# OBD-2_ESP32_Shield.net
KiCad netlist of a schematic drawn in Altium Designer
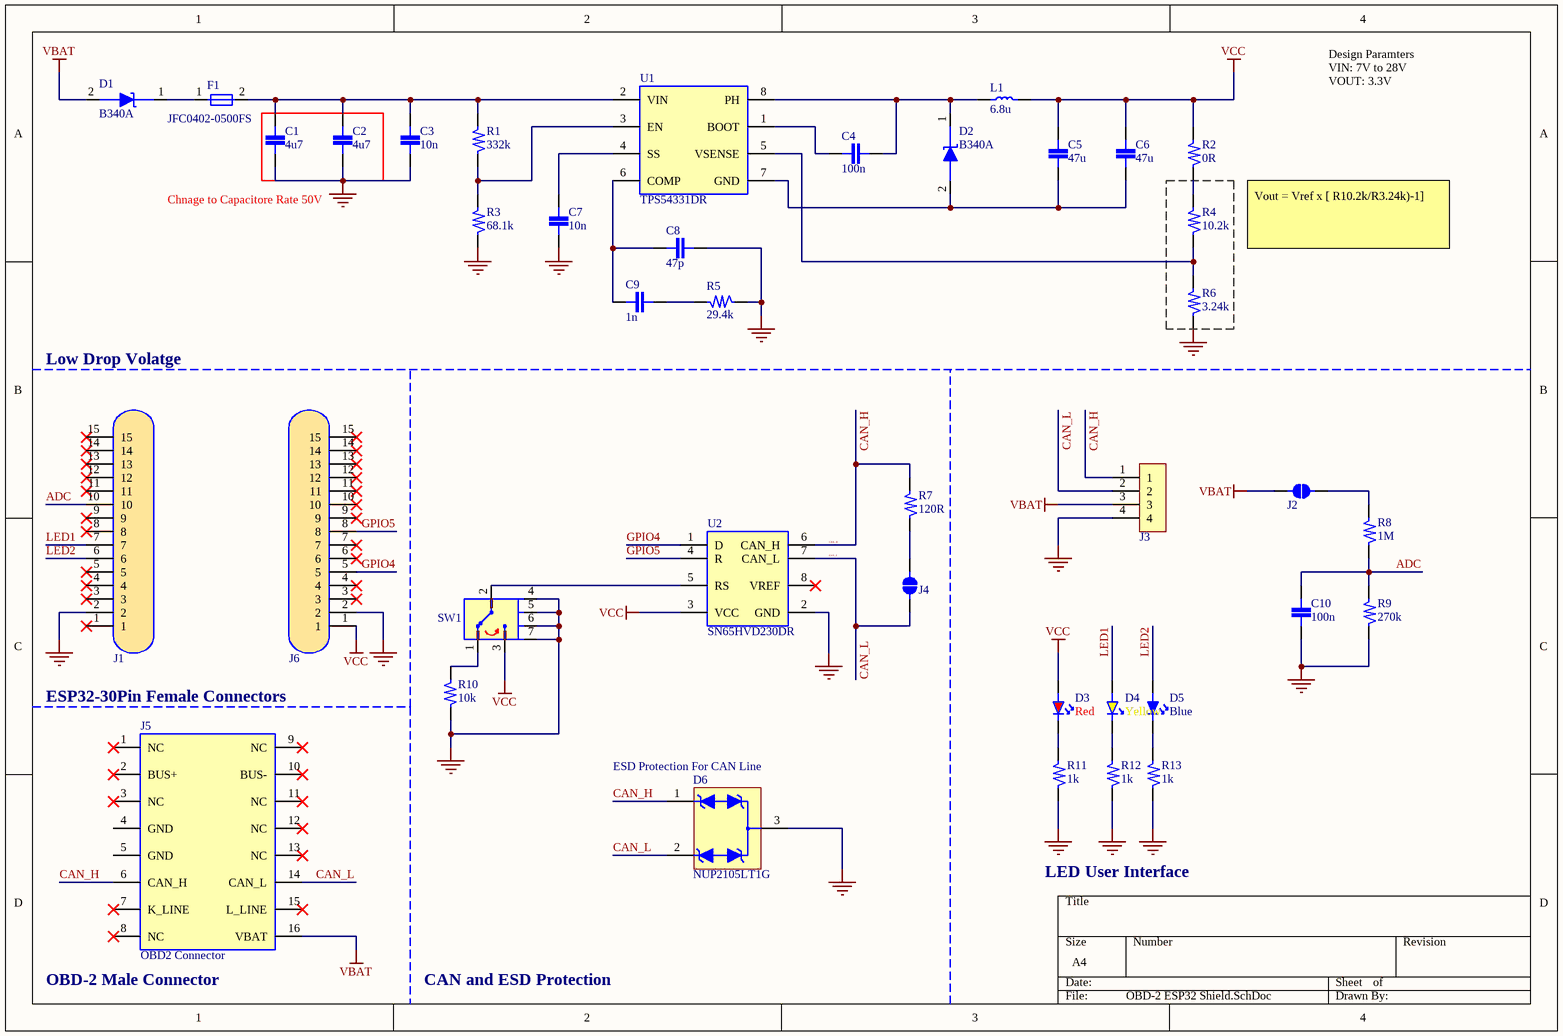
[diagram p0: OBD-2 ESP32 Shield.SchDoc]

(export (version "E")
  (design (tool "Eeschema 10.0.6"))
  (components
    (comp (ref "C1")
      (value "4u7")
      (footprint "CAP0402_1005")
      (description "25V 4.7uF X5R 0402 Multilayer Ceramic Capacitors MLCC - SMD/SMT ROHS")
      (fields (field (name "LCSC PART #") "C2858031") (field (name "MFR.PART #") "GRM155R61E475ME15D"))
      (libsource (lib "LeLibrary") (part "GRM155R61E475ME15D"))
    )
    (comp (ref "C2")
      (value "4u7")
      (footprint "CAP0402_1005")
      (description "25V 4.7uF X5R 0402 Multilayer Ceramic Capacitors MLCC - SMD/SMT ROHS")
      (fields (field (name "LCSC PART #") "C2858031") (field (name "MFR.PART #") "GRM155R61E475ME15D"))
      (libsource (lib "LeLibrary") (part "GRM155R61E475ME15D"))
    )
    (comp (ref "C3")
      (value "10n")
      (footprint "CAP0402_1005")
      (description "25V 10nF X7R ±10% 0402 Multilayer Ceramic Capacitors MLCC - SMD/SMT ROHS")
      (fields (field (name "LCSC PART #") "C77013") (field (name "MFR. PART #") "GRM155R71E103KA01D"))
      (libsource (lib "LeLibrary") (part "GRM155R71E103KA01D"))
    )
    (comp (ref "C4")
      (value "100n")
      (footprint "CAP0402_1005")
      (description "100V 100nF X5R ±10% 0402 Multilayer Ceramic Capacitors MLCC - SMD/SMT ROHS")
      (fields (field (name "LCSC PART #") "C162178") (field (name "MFR. PART #") "GRM155R62A104KE14D"))
      (libsource (lib "") (part "GRM155R62A104KE14D_1"))
    )
    (comp (ref "C5")
      (value "47u")
      (footprint "RES0603_1608")
      (description "6.3V 47uF X5R ±20% 0603 Multilayer Ceramic Capacitors MLCC - SMD/SMT ROHS")
      (fields (field (name "LCSC PART #") "C140782") (field (name "MFR. PART #") "GRM188R60J476ME15D"))
      (libsource (lib "LeLibrary") (part "GRM188R60J476ME15D"))
    )
    (comp (ref "C6")
      (value "47u")
      (footprint "RES0603_1608")
      (description "6.3V 47uF X5R ±20% 0603 Multilayer Ceramic Capacitors MLCC - SMD/SMT ROHS")
      (fields (field (name "LCSC PART #") "C140782") (field (name "MFR. PART #") "GRM188R60J476ME15D"))
      (libsource (lib "LeLibrary") (part "GRM188R60J476ME15D"))
    )
    (comp (ref "C7")
      (value "10n")
      (footprint "CAP0402_1005")
      (description "25V 10nF X7R ±10% 0402 Multilayer Ceramic Capacitors MLCC - SMD/SMT ROHS")
      (fields (field (name "LCSC PART #") "C77013") (field (name "MFR. PART #") "GRM155R71E103KA01D"))
      (libsource (lib "LeLibrary") (part "GRM155R71E103KA01D"))
    )
    (comp (ref "C8")
      (value "47p")
      (footprint "CAP0201_0603")
      (description "50V 47pF X7R ±10% 0201 Multilayer Ceramic Capacitors MLCC - SMD/SMT ROHS")
      (fields (field (name "LCSC PART #") "C576697") (field (name "MFR. PART #") "CC0201KRX7R9BB470"))
      (libsource (lib "LeLibrary") (part "CC0201KRX7R9BB470"))
    )
    (comp (ref "C9")
      (value "1n")
      (footprint "CAP0402_1005")
      (description "50V 1nF X8L ±10% 0402 Multilayer Ceramic Capacitors MLCC - SMD/SMT ROHS")
      (fields (field (name "MFR. PART #") "GCM155L81H102KA37D") (field (name "LCSC PART #") "C701290"))
      (libsource (lib "LeLibrary") (part "GCM155L81H102KA37D"))
    )
    (comp (ref "C10")
      (value "100n")
      (footprint "CAP0402_1005")
      (description "100V 100nF X5R ±10% 0402 Multilayer Ceramic Capacitors MLCC - SMD/SMT ROHS")
      (fields (field (name "LCSC PART #") "C162178") (field (name "MFR. PART #") "GRM155R62A104KE14D"))
      (libsource (lib "LeLibrary") (part "GRM155R62A104KE14D"))
    )
    (comp (ref "D1")
      (value "B340A")
      (footprint "SMA(DO-214AC)")
      (description "40V 3A 550mV@3A SMA(DO-214AC) Schottky Barrier Diodes (SBD) ROHS")
      (fields (field (name "LCSC PART #") "C3018525") (field (name "MFR.PART #") "B340A"))
      (libsource (lib "LeLibrary") (part "B340A"))
    )
    (comp (ref "D2")
      (value "B340A")
      (footprint "SMA(DO-214AC)")
      (description "40V 3A 550mV@3A SMA(DO-214AC) Schottky Barrier Diodes (SBD) ROHS")
      (fields (field (name "LCSC PART #") "C3018525") (field (name "MFR.PART #") "B340A"))
      (libsource (lib "LeLibrary") (part "B340A"))
    )
    (comp (ref "D3")
      (value "Red")
      (footprint "LED0603")
      (fields (field (name "LCSC PART #") "C965849") (field (name "MFR. PART #") "XL-TD1608SURC"))
      (libsource (lib "LeLibrary") (part "XL-TD1608SURC"))
    )
    (comp (ref "D4")
      (value "Yellow")
      (footprint "LED0603")
      (fields (field (name "LCSC PART #") "C965850") (field (name "MFR. PART #") "XL-TD1608UYC"))
      (libsource (lib "LeLibrary") (part "XL-TD1608UYC"))
    )
    (comp (ref "D5")
      (value "Blue")
      (footprint "LED0603")
      (fields (field (name "LCSC PART #") "C965853") (field (name "MFR. PART #") "XL-TD1608UBC"))
      (libsource (lib "LeLibrary") (part "XL-TD1608UBC"))
    )
    (comp (ref "D6")
      (value "NUP2105LT1G")
      (footprint "SOT-23")
      (description "SOT-23 Electrostatic and Surge Protection (TVS/ESD) ROHS")
      (fields (field (name "LCSC PART #") "C2890118") (field (name "MFR.PART #") "NUP2105LT1G"))
      (libsource (lib "LeLibrary") (part "NUP2105LT1G"))
    )
    (comp (ref "F1")
      (value "JFC0402-0500FS")
      (footprint "Fuse SMD 0402")
      (description "35A SMD Fuse 500mA 32V 32V 0402 Fuses ROHS")
      (fields (field (name "LCSC PART #") "C136320") (field (name "MFR.PART #") "JFC0402-0500FS"))
      (libsource (lib "LeLibrary") (part "JFC0402-0500FS"))
    )
    (comp (ref "J1")
      (value "Conn 1x15, 2.45mm")
      (footprint "1-Row, 15-Position, 2.54mm")
      (description "Header Connector 1x15, 2.54mm")
      (libsource (lib "LeLibrary") (part "Header Connector 1x15, 2.54mm"))
    )
    (comp (ref "J2")
      (value "Jumper")
      (footprint "JP0603")
      (description "Jumer 0604")
      (libsource (lib "LeLibrary") (part "Jumper"))
    )
    (comp (ref "J3")
      (value "HCZZ0139-4")
      (footprint "Connector Push-Pull, 2.54mm")
      (description "Connector Push-Pull, 4PIN, 2.5mm")
      (fields (field (name "LCSC PART #") "C7433739"))
      (libsource (lib "LeLibrary") (part "HCZZ0139-4"))
    )
    (comp (ref "J4")
      (value "Jumper")
      (footprint "JP0603")
      (description "Jumer 0604")
      (libsource (lib "LeLibrary") (part "Jumper"))
    )
    (comp (ref "J5")
      (value "OBD2 Connector")
      (footprint "COMTECH_C-OBD-II-16M")
      (description "16Pin, 2Row, 3.2mm, 4mm")
      (libsource (lib "LeLibrary") (part "OBD2 Connector"))
    )
    (comp (ref "J6")
      (value "Conn 1x15, 2.45mm")
      (footprint "1-Row, 15-Position, 2.54mm")
      (description "Header Connector 1x15, 2.54mm")
      (libsource (lib "LeLibrary") (part "Header Connector 1x15, 2.54mm"))
    )
    (comp (ref "L1")
      (value "6.8u")
      (footprint "SMD,5.8x5.2mm")
      (description "2.4A 6.8uH ±20% 58.5mΩ SMD,5.8x5.2mm Inductors (SMD) ROHS")
      (fields (field (name "LCSC PART #") "C2929430") (field (name "MFR. PART #") "CY54-6.8UH"))
      (libsource (lib "LeLibrary") (part "CY54-6.8UH"))
    )
    (comp (ref "R1")
      (value "332k")
      (footprint "RES0402_1005")
      (description "62.5mW Thick Film Resistors 50V ±100ppm/℃ ±1% 332kΩ 0402 Chip Resistor - Surface Mount ROHS")
      (fields (field (name "LCSC PART #") "C138005") (field (name "MFR.PART #") "RC0402FR-07332KL"))
      (libsource (lib "LeLibrary") (part "RC0402FR-07332KL"))
    )
    (comp (ref "R2")
      (value "0R")
      (footprint "RES0402_1005")
      (description "62.5mW ±150ppm/℃ 0Ω 0402 Chip Resistor - Surface Mount ROHS")
      (fields (field (name "LCSC PART #") "C4044221") (field (name "MFR. PART #") "PA0402-R-070RL"))
      (libsource (lib "LeLibrary") (part "PA0402-R-070RL"))
    )
    (comp (ref "R3")
      (value "68.1k")
      (footprint "RES0402_1005")
      (description "62.5mW Thick Film Resistors 50V ±100ppm/℃ ±1% 68.1kΩ 0402 Chip Resistor - Surface Mount ROHS")
      (fields (field (name "LCSC PART #") "C276276") (field (name "MFR.PART #") "RC0402FR-0768K1L"))
      (libsource (lib "LeLibrary") (part "RC0402FR-0768K1L"))
    )
    (comp (ref "R4")
      (value "10.2k")
      (footprint "RES0402_1005")
      (description "62.5mW Thin Film Resistor 50V ±25ppm/℃ ±0.1% 10.2kΩ 0402 Chip Resistor - Surface Mount ROHS")
      (fields (field (name "LCSC PART #") "C852479") (field (name "MFR. PART #") "RT0402BRD0710K2L"))
      (libsource (lib "LeLibrary") (part "RT0402BRD0710K2L"))
    )
    (comp (ref "R5")
      (value "29.4k")
      (footprint "RES0402_1005")
      (description "63mW Thin Film Resistor ±0.5% ±25ppm/℃ 29.4kΩ 0402 Chip Resistor - Surface Mount ROHS")
      (fields (field (name "LCSC PART #") "C851325") (field (name "MFR. PART #") "AT0402DRD0729K4L"))
      (libsource (lib "LeLibrary") (part "AT0402DRD0729K4L"))
    )
    (comp (ref "R6")
      (value "3.24k")
      (footprint "RES0402_1005")
      (description "63mW Thin Film Resistor ±0.5% ±25ppm/℃ 3.24kΩ 0402 Chip Resistor - Surface Mount ROHS")
      (fields (field (name "LCSC PART #") "C851383") (field (name "MFR. PART #") "AT0402DRD073K24L"))
      (libsource (lib "LeLibrary") (part "AT0402DRD073K24L"))
    )
    (comp (ref "R7")
      (value "120R")
      (footprint "RES0402_1005")
      (description "62.5mW Thin Film Resistor ±50ppm/℃ ±1% 120Ω 0402 Chip Resistor - Surface Mount ROHS")
      (fields (field (name "LCSC PART #") "C854098") (field (name "MFR. PART #") "RT0402FRE07120RL"))
      (libsource (lib "LeLibrary") (part "RT0402FRE07120RL"))
    )
    (comp (ref "R8")
      (value "1M")
      (footprint "RES0402_1005")
      (description "62.5mW Thick Film Resistors 50V ±100ppm/℃ ±5% 1MΩ 0402 Chip Resistor - Surface Mount ROHS")
      (fields (field (name "LCSC PART #") "C93949") (field (name "MFR. PART #") "RC0402JR-071ML"))
      (libsource (lib "LeLibrary") (part "RC0402JR-071ML"))
    )
    (comp (ref "R9")
      (value "270k")
      (footprint "RES0402_1005")
      (description "62.5mW Thick Film Resistors 50V ±100ppm/℃ ±1% 270kΩ 0402 Chip Resistor - Surface Mount ROHS")
      (fields (field (name "LCSC PART #") "C163475") (field (name "MFR. PART #") "RC0402FR-07270KL"))
      (libsource (lib "LeLibrary") (part "RC0402FR-07270KL"))
    )
    (comp (ref "R10")
      (value "10k")
      (footprint "RES0402_1005")
      (description "62.5mW Thin Film Resistor ±0.5% ±25ppm/℃ 10kΩ 0402 Chip Resistor - Surface Mount ROHS")
      (fields (field (name "LCSC PART #") "C853514") (field (name "MFR. PART #") "RT0402DRD0710KL"))
      (libsource (lib "LeLibrary") (part "RT0402DRD0710KL"))
    )
    (comp (ref "R11")
      (value "1k")
      (footprint "RES0402_1005")
      (description "62.5mW Thin Film Resistor 50V ±50ppm/℃ ±0.1% 1kΩ 0402 Chip Resistor - Surface Mount ROHS")
      (fields (field (name "LCSC PART #") "C513664") (field (name "MFR. PART #") "RT0402BRE071KL"))
      (libsource (lib "LeLibrary") (part "RT0402BRE071KL"))
    )
    (comp (ref "R12")
      (value "1k")
      (footprint "RES0402_1005")
      (description "62.5mW Thin Film Resistor 50V ±50ppm/℃ ±0.1% 1kΩ 0402 Chip Resistor - Surface Mount ROHS")
      (fields (field (name "LCSC PART #") "C513664") (field (name "MFR. PART #") "RT0402BRE071KL"))
      (libsource (lib "LeLibrary") (part "RT0402BRE071KL"))
    )
    (comp (ref "R13")
      (value "1k")
      (footprint "RES0402_1005")
      (description "62.5mW Thin Film Resistor 50V ±50ppm/℃ ±0.1% 1kΩ 0402 Chip Resistor - Surface Mount ROHS")
      (fields (field (name "LCSC PART #") "C513664") (field (name "MFR. PART #") "RT0402BRE071KL"))
      (libsource (lib "LeLibrary") (part "RT0402BRE071KL"))
    )
    (comp (ref "SW1")
      (value "SSSS811101")
      (footprint "SMD-Switch")
      (description "300mA Surface Mount，Right Angle SPDT 5V 1万次 SMD Slide Switches ROHS")
      (fields (field (name "LCSC PART #") "C109335"))
      (libsource (lib "LeLibrary") (part "SSSS811101"))
    )
    (comp (ref "U1")
      (value "TPS54331DR")
      (footprint "SOIC-8")
      (description "Step-down type Adjustable 800mV~25V 3A 3.5V~28V SOIC-8 DC-DC Converters ROHS")
      (fields (field (name "LCSC PART #") "C9865") (field (name "MFR.PART #") "TPS54331DR"))
      (libsource (lib "LeLibrary") (part "TPS54331DR"))
    )
    (comp (ref "U2")
      (value "SN65HVD230DR")
      (footprint "SOIC-8")
      (description "1Mbps Transceiver SOIC-8 CAN ICs ROHS")
      (fields (field (name "LCSC PART #") "C12084") (field (name "MFR.PART #") "SN65HVD230DR"))
      (libsource (lib "LeLibrary") (part "SN65HVD230DR"))
    )
  )
  (nets
    (net (code "1") (name "/ADC") (class "Default")
      (node (ref "C10") (pin "2") (pinfunction "2_2") (pintype "passive"))
      (node (ref "J1") (pin "10") (pinfunction "10_10") (pintype "passive"))
      (node (ref "R8") (pin "1") (pinfunction "1_1") (pintype "passive"))
      (node (ref "R9") (pin "2") (pinfunction "2_2") (pintype "passive"))
    )
    (net (code "2") (name "/CAN_H") (class "Default")
      (node (ref "D6") (pin "1") (pinfunction "C_1") (pintype "passive"))
      (node (ref "J3") (pin "1") (pinfunction "1_1") (pintype "passive"))
      (node (ref "J5") (pin "6") (pinfunction "CAN_H_6") (pintype "passive"))
      (node (ref "R7") (pin "2") (pinfunction "2_2") (pintype "passive"))
      (node (ref "U2") (pin "6") (pinfunction "CAN_H_6") (pintype "passive"))
    )
    (net (code "3") (name "/CAN_L") (class "Default")
      (node (ref "D6") (pin "2") (pinfunction "C_2") (pintype "passive"))
      (node (ref "J3") (pin "2") (pinfunction "2_2") (pintype "passive"))
      (node (ref "J4") (pin "1") (pinfunction "1_1") (pintype "passive"))
      (node (ref "J5") (pin "14") (pinfunction "CAN_L_14") (pintype "passive"))
      (node (ref "U2") (pin "7") (pinfunction "CAN_L_7") (pintype "passive"))
    )
    (net (code "4") (name "/GPIO4") (class "Default")
      (node (ref "J6") (pin "5") (pinfunction "5_5") (pintype "passive"))
      (node (ref "U2") (pin "1") (pinfunction "D_1") (pintype "passive"))
    )
    (net (code "5") (name "/GPIO5") (class "Default")
      (node (ref "J6") (pin "8") (pinfunction "8_8") (pintype "passive"))
      (node (ref "U2") (pin "4") (pinfunction "R_4") (pintype "passive"))
    )
    (net (code "6") (name "/LED1") (class "Default")
      (node (ref "D4") (pin "1") (pinfunction "1_1") (pintype "passive"))
      (node (ref "J1") (pin "7") (pinfunction "7_7") (pintype "passive"))
    )
    (net (code "7") (name "/LED2") (class "Default")
      (node (ref "D5") (pin "1") (pinfunction "1_1") (pintype "passive"))
      (node (ref "J1") (pin "6") (pinfunction "6_6") (pintype "passive"))
    )
    (net (code "8") (name "GND") (class "Default")
      (node (ref "C1") (pin "1") (pinfunction "1_1") (pintype "passive"))
      (node (ref "C10") (pin "1") (pinfunction "1_1") (pintype "passive"))
      (node (ref "C2") (pin "1") (pinfunction "1_1") (pintype "passive"))
      (node (ref "C3") (pin "1") (pinfunction "1_1") (pintype "passive"))
      (node (ref "C7") (pin "1") (pinfunction "1_1") (pintype "passive"))
      (node (ref "C8") (pin "1") (pinfunction "1_1") (pintype "passive"))
      (node (ref "D6") (pin "3") (pinfunction "A_3") (pintype "passive"))
      (node (ref "J1") (pin "2") (pinfunction "2_2") (pintype "passive"))
      (node (ref "J3") (pin "4") (pinfunction "4_4") (pintype "passive"))
      (node (ref "J6") (pin "2") (pinfunction "2_2") (pintype "passive"))
      (node (ref "R10") (pin "2") (pinfunction "2_2") (pintype "passive"))
      (node (ref "R11") (pin "1") (pinfunction "1_1") (pintype "passive"))
      (node (ref "R12") (pin "1") (pinfunction "1_1") (pintype "passive"))
      (node (ref "R13") (pin "1") (pinfunction "1_1") (pintype "passive"))
      (node (ref "R3") (pin "1") (pinfunction "1_1") (pintype "passive"))
      (node (ref "R5") (pin "1") (pinfunction "1_1") (pintype "passive"))
      (node (ref "R6") (pin "1") (pinfunction "1_1") (pintype "passive"))
      (node (ref "R9") (pin "1") (pinfunction "1_1") (pintype "passive"))
      (node (ref "SW1") (pin "4") (pinfunction "4_4") (pintype "passive"))
      (node (ref "SW1") (pin "5") (pinfunction "5_5") (pintype "passive"))
      (node (ref "SW1") (pin "6") (pinfunction "6_6") (pintype "passive"))
      (node (ref "SW1") (pin "7") (pinfunction "7_7") (pintype "passive"))
      (node (ref "U2") (pin "2") (pinfunction "GND_2") (pintype "passive"))
    )
    (net (code "9") (name "Net-(C9-Pad1)") (class "Default")
      (node (ref "C9") (pin "1") (pinfunction "1_1") (pintype "passive"))
      (node (ref "R5") (pin "2") (pinfunction "2_2") (pintype "passive"))
    )
    (net (code "10") (name "Net-(D1-cathode)") (class "Default")
      (node (ref "D1") (pin "1") (pinfunction "cathode_1") (pintype "passive"))
      (node (ref "F1") (pin "1") (pinfunction "1_1") (pintype "passive"))
    )
    (net (code "11") (name "Net-(D2-anode)") (class "Default")
      (node (ref "C5") (pin "1") (pinfunction "1_1") (pintype "passive"))
      (node (ref "C6") (pin "1") (pinfunction "1_1") (pintype "passive"))
      (node (ref "D2") (pin "2") (pinfunction "anode_2") (pintype "passive"))
      (node (ref "U1") (pin "7") (pinfunction "GND_7") (pintype "passive"))
    )
    (net (code "12") (name "Net-(D2-cathode)") (class "Default")
      (node (ref "C4") (pin "2") (pinfunction "2_2") (pintype "passive"))
      (node (ref "D2") (pin "1") (pinfunction "cathode_1") (pintype "passive"))
      (node (ref "L1") (pin "1") (pinfunction "1_1") (pintype "passive"))
      (node (ref "U1") (pin "8") (pinfunction "PH_8") (pintype "passive"))
    )
    (net (code "13") (name "Net-(D3-Pad2)") (class "Default")
      (node (ref "D3") (pin "2") (pinfunction "2_2") (pintype "passive"))
      (node (ref "R11") (pin "2") (pinfunction "2_2") (pintype "passive"))
    )
    (net (code "14") (name "Net-(D4-Pad2)") (class "Default")
      (node (ref "D4") (pin "2") (pinfunction "2_2") (pintype "passive"))
      (node (ref "R12") (pin "2") (pinfunction "2_2") (pintype "passive"))
    )
    (net (code "15") (name "Net-(D5-Pad2)") (class "Default")
      (node (ref "D5") (pin "2") (pinfunction "2_2") (pintype "passive"))
      (node (ref "R13") (pin "2") (pinfunction "2_2") (pintype "passive"))
    )
    (net (code "16") (name "Net-(J2-Pad2)") (class "Default")
      (node (ref "J2") (pin "2") (pinfunction "2_2") (pintype "passive"))
      (node (ref "R8") (pin "2") (pinfunction "2_2") (pintype "passive"))
    )
    (net (code "17") (name "Net-(J4-Pad2)") (class "Default")
      (node (ref "J4") (pin "2") (pinfunction "2_2") (pintype "passive"))
      (node (ref "R7") (pin "1") (pinfunction "1_1") (pintype "passive"))
    )
    (net (code "18") (name "Net-(R2-Pad1)") (class "Default")
      (node (ref "R2") (pin "1") (pinfunction "1_1") (pintype "passive"))
      (node (ref "R4") (pin "2") (pinfunction "2_2") (pintype "passive"))
    )
    (net (code "19") (name "Net-(R10-Pad1)") (class "Default")
      (node (ref "R10") (pin "1") (pinfunction "1_1") (pintype "passive"))
      (node (ref "SW1") (pin "1") (pinfunction "1_1") (pintype "passive"))
    )
    (net (code "20") (name "Net-(U1-BOOT)") (class "Default")
      (node (ref "C4") (pin "1") (pinfunction "1_1") (pintype "passive"))
      (node (ref "U1") (pin "1") (pinfunction "BOOT_1") (pintype "passive"))
    )
    (net (code "21") (name "Net-(U1-COMP)") (class "Default")
      (node (ref "C8") (pin "2") (pinfunction "2_2") (pintype "passive"))
      (node (ref "C9") (pin "2") (pinfunction "2_2") (pintype "passive"))
      (node (ref "U1") (pin "6") (pinfunction "COMP_6") (pintype "passive"))
    )
    (net (code "22") (name "Net-(U1-EN)") (class "Default")
      (node (ref "R1") (pin "1") (pinfunction "1_1") (pintype "passive"))
      (node (ref "R3") (pin "2") (pinfunction "2_2") (pintype "passive"))
      (node (ref "U1") (pin "3") (pinfunction "EN_3") (pintype "passive"))
    )
    (net (code "23") (name "Net-(U1-SS)") (class "Default")
      (node (ref "C7") (pin "2") (pinfunction "2_2") (pintype "passive"))
      (node (ref "U1") (pin "4") (pinfunction "SS_4") (pintype "passive"))
    )
    (net (code "24") (name "Net-(U1-VIN)") (class "Default")
      (node (ref "C1") (pin "2") (pinfunction "2_2") (pintype "passive"))
      (node (ref "C2") (pin "2") (pinfunction "2_2") (pintype "passive"))
      (node (ref "C3") (pin "2") (pinfunction "2_2") (pintype "passive"))
      (node (ref "F1") (pin "2") (pinfunction "2_2") (pintype "passive"))
      (node (ref "R1") (pin "2") (pinfunction "2_2") (pintype "passive"))
      (node (ref "U1") (pin "2") (pinfunction "VIN_2") (pintype "passive"))
    )
    (net (code "25") (name "Net-(U1-VSENSE)") (class "Default")
      (node (ref "R4") (pin "1") (pinfunction "1_1") (pintype "passive"))
      (node (ref "R6") (pin "2") (pinfunction "2_2") (pintype "passive"))
      (node (ref "U1") (pin "5") (pinfunction "VSENSE_5") (pintype "passive"))
    )
    (net (code "26") (name "Net-(U2-RS)") (class "Default")
      (node (ref "SW1") (pin "2") (pinfunction "2_2") (pintype "passive"))
      (node (ref "U2") (pin "5") (pinfunction "RS_5") (pintype "passive"))
    )
    (net (code "27") (name "VBAT") (class "Default")
      (node (ref "D1") (pin "2") (pinfunction "anode_2") (pintype "passive"))
      (node (ref "J2") (pin "1") (pinfunction "1_1") (pintype "passive"))
      (node (ref "J3") (pin "3") (pinfunction "3_3") (pintype "passive"))
      (node (ref "J5") (pin "16") (pinfunction "VBAT_16") (pintype "passive"))
    )
    (net (code "28") (name "VCC") (class "Default")
      (node (ref "C5") (pin "2") (pinfunction "2_2") (pintype "passive"))
      (node (ref "C6") (pin "2") (pinfunction "2_2") (pintype "passive"))
      (node (ref "D3") (pin "1") (pinfunction "1_1") (pintype "passive"))
      (node (ref "J6") (pin "1") (pinfunction "1_1") (pintype "passive"))
      (node (ref "L1") (pin "2") (pinfunction "2_2") (pintype "passive"))
      (node (ref "R2") (pin "2") (pinfunction "2_2") (pintype "passive"))
      (node (ref "SW1") (pin "3") (pinfunction "3_3") (pintype "passive"))
      (node (ref "U2") (pin "3") (pinfunction "VCC_3") (pintype "passive"))
    )
    (net (code "29") (name "unconnected-(J1-Pad1)") (class "Default")
      (node (ref "J1") (pin "1") (pinfunction "1_1") (pintype "passive+no_connect"))
    )
    (net (code "30") (name "unconnected-(J1-Pad3)") (class "Default")
      (node (ref "J1") (pin "3") (pinfunction "3_3") (pintype "passive+no_connect"))
    )
    (net (code "31") (name "unconnected-(J1-Pad4)") (class "Default")
      (node (ref "J1") (pin "4") (pinfunction "4_4") (pintype "passive+no_connect"))
    )
    (net (code "32") (name "unconnected-(J1-Pad5)") (class "Default")
      (node (ref "J1") (pin "5") (pinfunction "5_5") (pintype "passive+no_connect"))
    )
    (net (code "33") (name "unconnected-(J1-Pad8)") (class "Default")
      (node (ref "J1") (pin "8") (pinfunction "8_8") (pintype "passive+no_connect"))
    )
    (net (code "34") (name "unconnected-(J1-Pad9)") (class "Default")
      (node (ref "J1") (pin "9") (pinfunction "9_9") (pintype "passive+no_connect"))
    )
    (net (code "35") (name "unconnected-(J1-Pad11)") (class "Default")
      (node (ref "J1") (pin "11") (pinfunction "11_11") (pintype "passive+no_connect"))
    )
    (net (code "36") (name "unconnected-(J1-Pad12)") (class "Default")
      (node (ref "J1") (pin "12") (pinfunction "12_12") (pintype "passive+no_connect"))
    )
    (net (code "37") (name "unconnected-(J1-Pad13)") (class "Default")
      (node (ref "J1") (pin "13") (pinfunction "13_13") (pintype "passive+no_connect"))
    )
    (net (code "38") (name "unconnected-(J1-Pad14)") (class "Default")
      (node (ref "J1") (pin "14") (pinfunction "14_14") (pintype "passive+no_connect"))
    )
    (net (code "39") (name "unconnected-(J1-Pad15)") (class "Default")
      (node (ref "J1") (pin "15") (pinfunction "15_15") (pintype "passive+no_connect"))
    )
    (net (code "40") (name "unconnected-(J5-BUS+-Pad2)") (class "Default")
      (node (ref "J5") (pin "2") (pinfunction "BUS+_2") (pintype "passive+no_connect"))
    )
    (net (code "41") (name "unconnected-(J5-BUS--Pad10)") (class "Default")
      (node (ref "J5") (pin "10") (pinfunction "BUS-_10") (pintype "passive+no_connect"))
    )
    (net (code "42") (name "unconnected-(J5-GND-Pad4)") (class "Default")
      (node (ref "J5") (pin "4") (pinfunction "GND_4") (pintype "passive"))
    )
    (net (code "43") (name "unconnected-(J5-GND-Pad5)") (class "Default")
      (node (ref "J5") (pin "5") (pinfunction "GND_5") (pintype "passive"))
    )
    (net (code "44") (name "unconnected-(J5-K_LINE-Pad7)") (class "Default")
      (node (ref "J5") (pin "7") (pinfunction "K_LINE_7") (pintype "passive+no_connect"))
    )
    (net (code "45") (name "unconnected-(J5-L_LINE-Pad15)") (class "Default")
      (node (ref "J5") (pin "15") (pinfunction "L_LINE_15") (pintype "passive+no_connect"))
    )
    (net (code "46") (name "unconnected-(J5-NC-Pad1)") (class "Default")
      (node (ref "J5") (pin "1") (pinfunction "NC_1") (pintype "passive+no_connect"))
    )
    (net (code "47") (name "unconnected-(J5-NC-Pad3)") (class "Default")
      (node (ref "J5") (pin "3") (pinfunction "NC_3") (pintype "passive+no_connect"))
    )
    (net (code "48") (name "unconnected-(J5-NC-Pad8)") (class "Default")
      (node (ref "J5") (pin "8") (pinfunction "NC_8") (pintype "passive+no_connect"))
    )
    (net (code "49") (name "unconnected-(J5-NC-Pad9)") (class "Default")
      (node (ref "J5") (pin "9") (pinfunction "NC_9") (pintype "passive+no_connect"))
    )
    (net (code "50") (name "unconnected-(J5-NC-Pad11)") (class "Default")
      (node (ref "J5") (pin "11") (pinfunction "NC_11") (pintype "passive+no_connect"))
    )
    (net (code "51") (name "unconnected-(J5-NC-Pad12)") (class "Default")
      (node (ref "J5") (pin "12") (pinfunction "NC_12") (pintype "passive+no_connect"))
    )
    (net (code "52") (name "unconnected-(J5-NC-Pad13)") (class "Default")
      (node (ref "J5") (pin "13") (pinfunction "NC_13") (pintype "passive+no_connect"))
    )
    (net (code "53") (name "unconnected-(J6-Pad3)") (class "Default")
      (node (ref "J6") (pin "3") (pinfunction "3_3") (pintype "passive+no_connect"))
    )
    (net (code "54") (name "unconnected-(J6-Pad4)") (class "Default")
      (node (ref "J6") (pin "4") (pinfunction "4_4") (pintype "passive+no_connect"))
    )
    (net (code "55") (name "unconnected-(J6-Pad6)") (class "Default")
      (node (ref "J6") (pin "6") (pinfunction "6_6") (pintype "passive+no_connect"))
    )
    (net (code "56") (name "unconnected-(J6-Pad7)") (class "Default")
      (node (ref "J6") (pin "7") (pinfunction "7_7") (pintype "passive+no_connect"))
    )
    (net (code "57") (name "unconnected-(J6-Pad9)") (class "Default")
      (node (ref "J6") (pin "9") (pinfunction "9_9") (pintype "passive+no_connect"))
    )
    (net (code "58") (name "unconnected-(J6-Pad10)") (class "Default")
      (node (ref "J6") (pin "10") (pinfunction "10_10") (pintype "passive+no_connect"))
    )
    (net (code "59") (name "unconnected-(J6-Pad11)") (class "Default")
      (node (ref "J6") (pin "11") (pinfunction "11_11") (pintype "passive+no_connect"))
    )
    (net (code "60") (name "unconnected-(J6-Pad12)") (class "Default")
      (node (ref "J6") (pin "12") (pinfunction "12_12") (pintype "passive+no_connect"))
    )
    (net (code "61") (name "unconnected-(J6-Pad13)") (class "Default")
      (node (ref "J6") (pin "13") (pinfunction "13_13") (pintype "passive+no_connect"))
    )
    (net (code "62") (name "unconnected-(J6-Pad14)") (class "Default")
      (node (ref "J6") (pin "14") (pinfunction "14_14") (pintype "passive+no_connect"))
    )
    (net (code "63") (name "unconnected-(J6-Pad15)") (class "Default")
      (node (ref "J6") (pin "15") (pinfunction "15_15") (pintype "passive+no_connect"))
    )
    (net (code "64") (name "unconnected-(U2-VREF-Pad8)") (class "Default")
      (node (ref "U2") (pin "8") (pinfunction "VREF_8") (pintype "passive+no_connect"))
    )
  )
)
